# LowVoltageShutdown.net
KiCad netlist of a schematic drawn in EAGLE
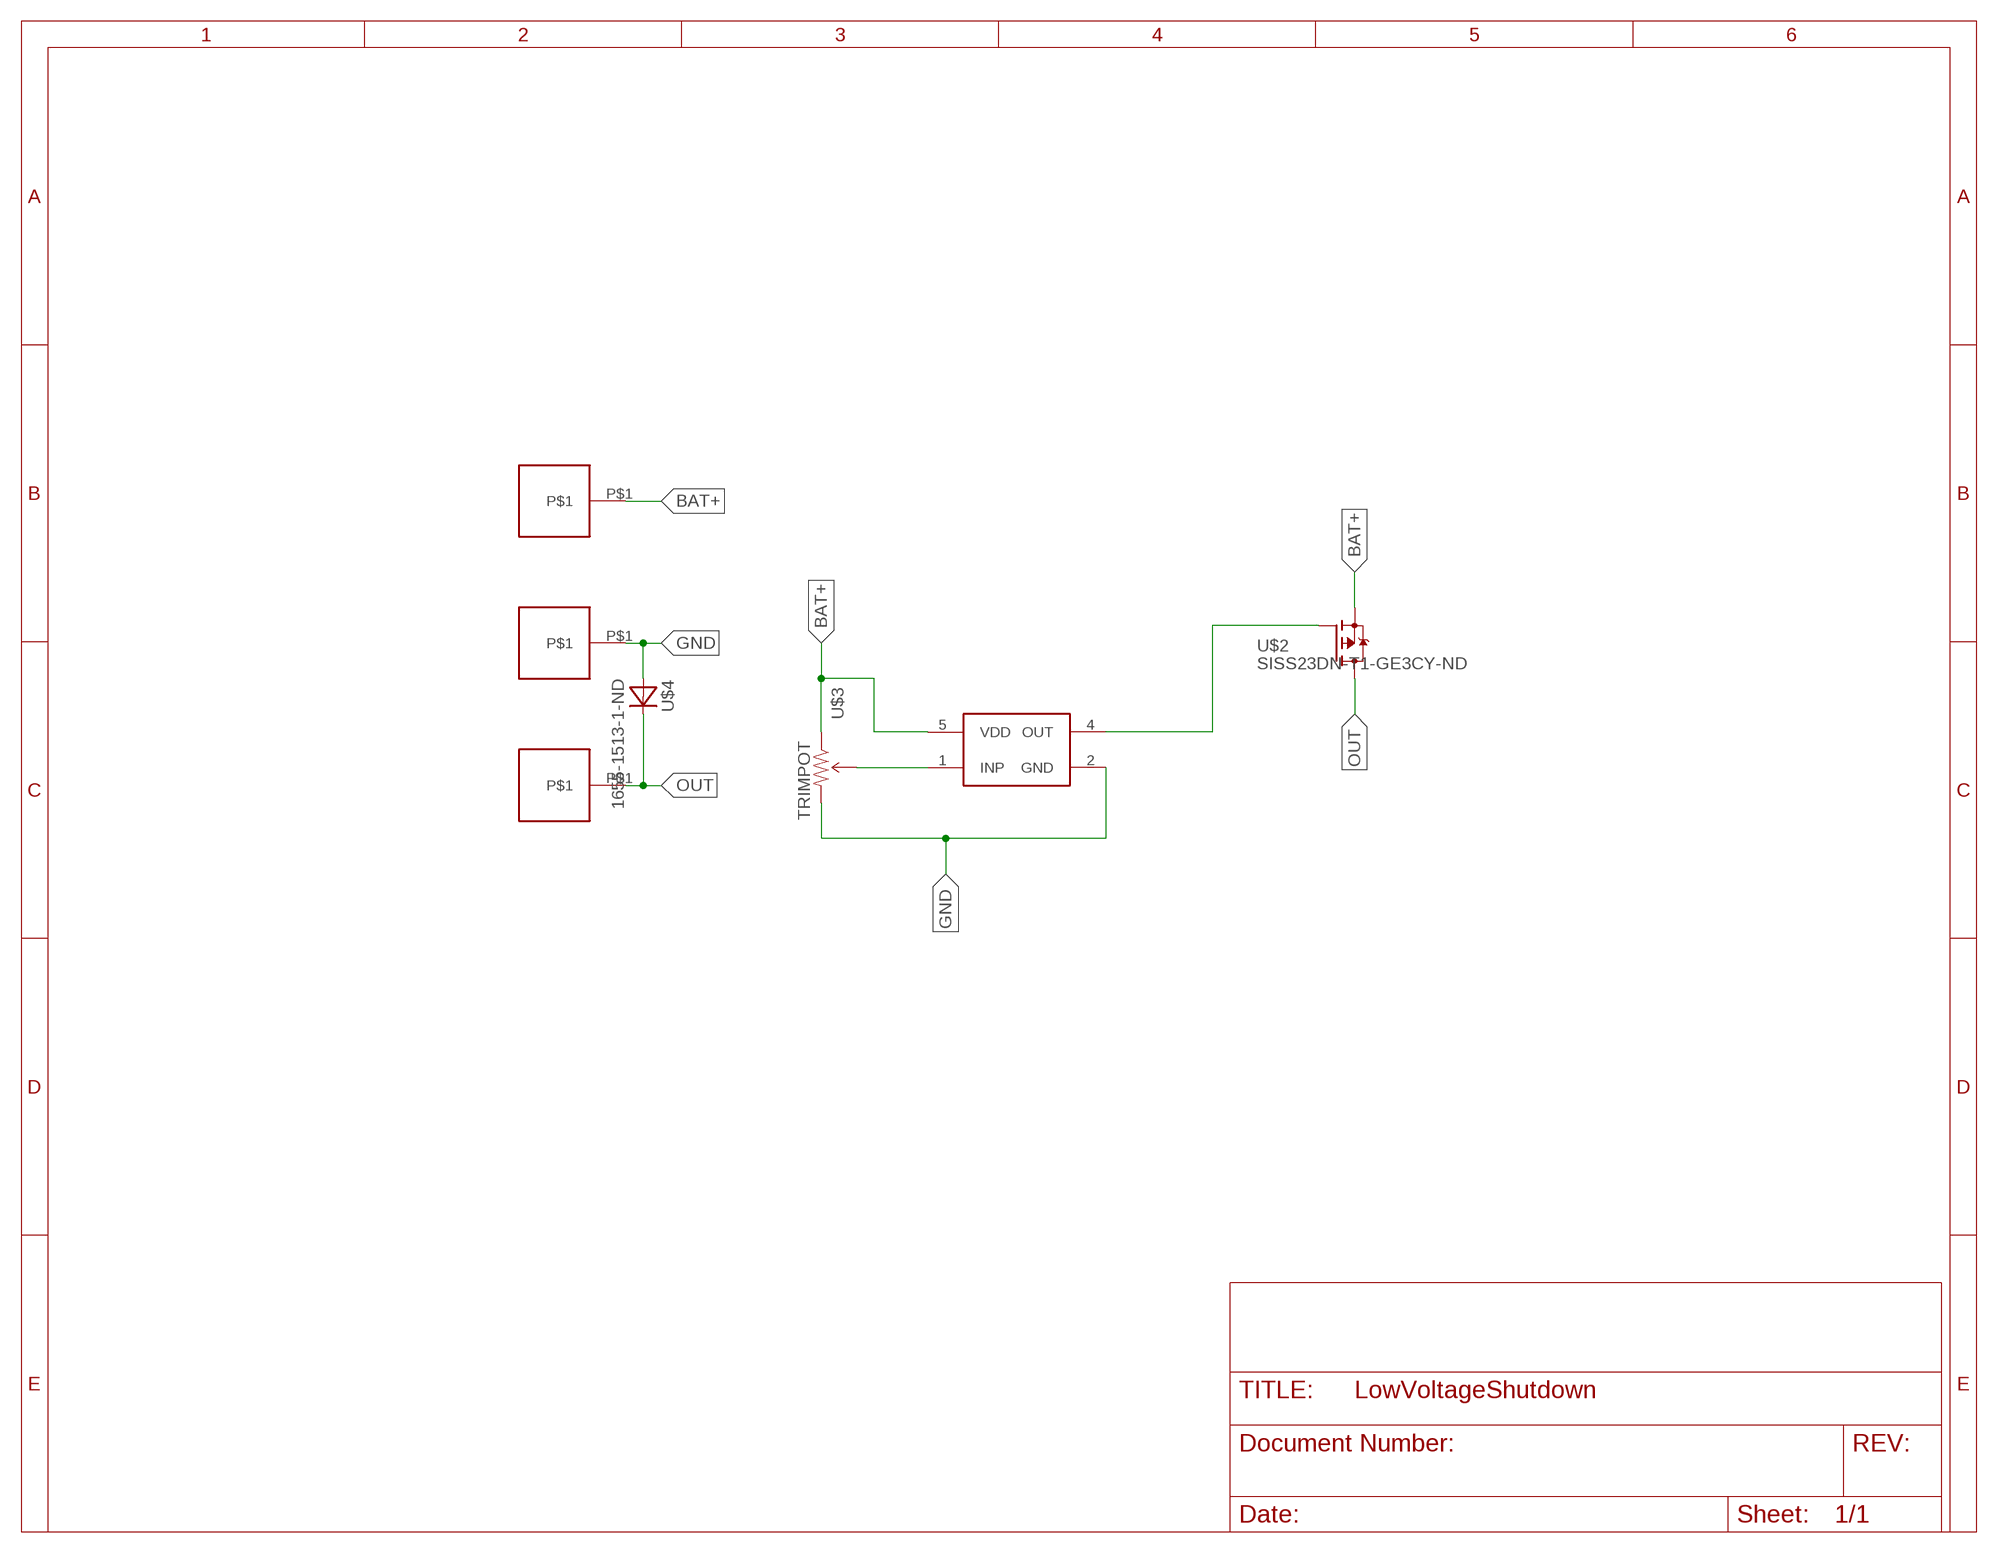
[diagram p0: schematic, sheet 1]

(export (version "E")
  (design (tool "Eeschema 10.0.6"))
  (components
    (comp (ref "BAT+")
      (value "16G")
      (footprint "eagle-import:16G")
      (libsource (lib "eagle-import") (part "16G"))
    )
    (comp (ref "GND")
      (value "16G")
      (footprint "eagle-import:16G")
      (libsource (lib "eagle-import") (part "16G"))
    )
    (comp (ref "OUT")
      (value "16G")
      (footprint "eagle-import:16G")
      (libsource (lib "eagle-import") (part "16G"))
    )
    (comp (ref "U$1")
      (value "MIC842L")
      (footprint "eagle-import:SC70")
      (libsource (lib "eagle-import") (part "MIC842L"))
    )
    (comp (ref "U$2")
      (value "SISS23DN-T1-GE3CY-ND")
      (footprint "eagle-import:POWERPAK1212-8S")
      (libsource (lib "eagle-import") (part "SISS23DN-T1-GE3CY-ND"))
    )
    (comp (ref "U$3")
      (value "TRIMPOT")
      (footprint "eagle-import:490-2877-ND")
      (libsource (lib "eagle-import") (part "TRIMPOT"))
    )
    (comp (ref "U$4")
      (value "1655-1513-1-ND")
      (footprint "eagle-import:1655-1513-1-ND")
      (libsource (lib "eagle-import") (part "1655-1513-1-ND"))
    )
  )
  (nets
    (net (code "1") (name "BAT+") (class "Default")
      (node (ref "BAT+") (pin "P$1") (pinfunction "P$1_P$1") (pintype "bidirectional"))
      (node (ref "U$1") (pin "5") (pinfunction "VDD_5") (pintype "bidirectional"))
      (node (ref "U$2") (pin "S") (pinfunction "S_S") (pintype "passive"))
      (node (ref "U$3") (pin "P$1") (pinfunction "CCW_P$1") (pintype "passive"))
    )
    (net (code "2") (name "GND") (class "Default")
      (node (ref "GND") (pin "P$1") (pinfunction "P$1_P$1") (pintype "bidirectional"))
      (node (ref "U$1") (pin "2") (pinfunction "GND_2") (pintype "bidirectional"))
      (node (ref "U$3") (pin "P$3") (pinfunction "CW_P$3") (pintype "passive"))
      (node (ref "U$4") (pin "A") (pinfunction "A_A") (pintype "passive"))
    )
    (net (code "3") (name "Net-(U$1-INP)") (class "Default")
      (node (ref "U$1") (pin "1") (pinfunction "INP_1") (pintype "bidirectional"))
      (node (ref "U$3") (pin "P$2") (pinfunction "WIPER_P$2") (pintype "passive"))
    )
    (net (code "4") (name "Net-(U$1-OUT)") (class "Default")
      (node (ref "U$1") (pin "4") (pinfunction "OUT_4") (pintype "bidirectional"))
      (node (ref "U$2") (pin "G") (pinfunction "G_G") (pintype "passive"))
    )
    (net (code "5") (name "OUT") (class "Default")
      (node (ref "OUT") (pin "P$1") (pinfunction "P$1_P$1") (pintype "bidirectional"))
      (node (ref "U$2") (pin "D") (pinfunction "D_D") (pintype "passive"))
      (node (ref "U$4") (pin "C") (pinfunction "C_C") (pintype "passive"))
    )
  )
)
